# withcc3200.net
KiCad netlist of a schematic drawn in EAGLE
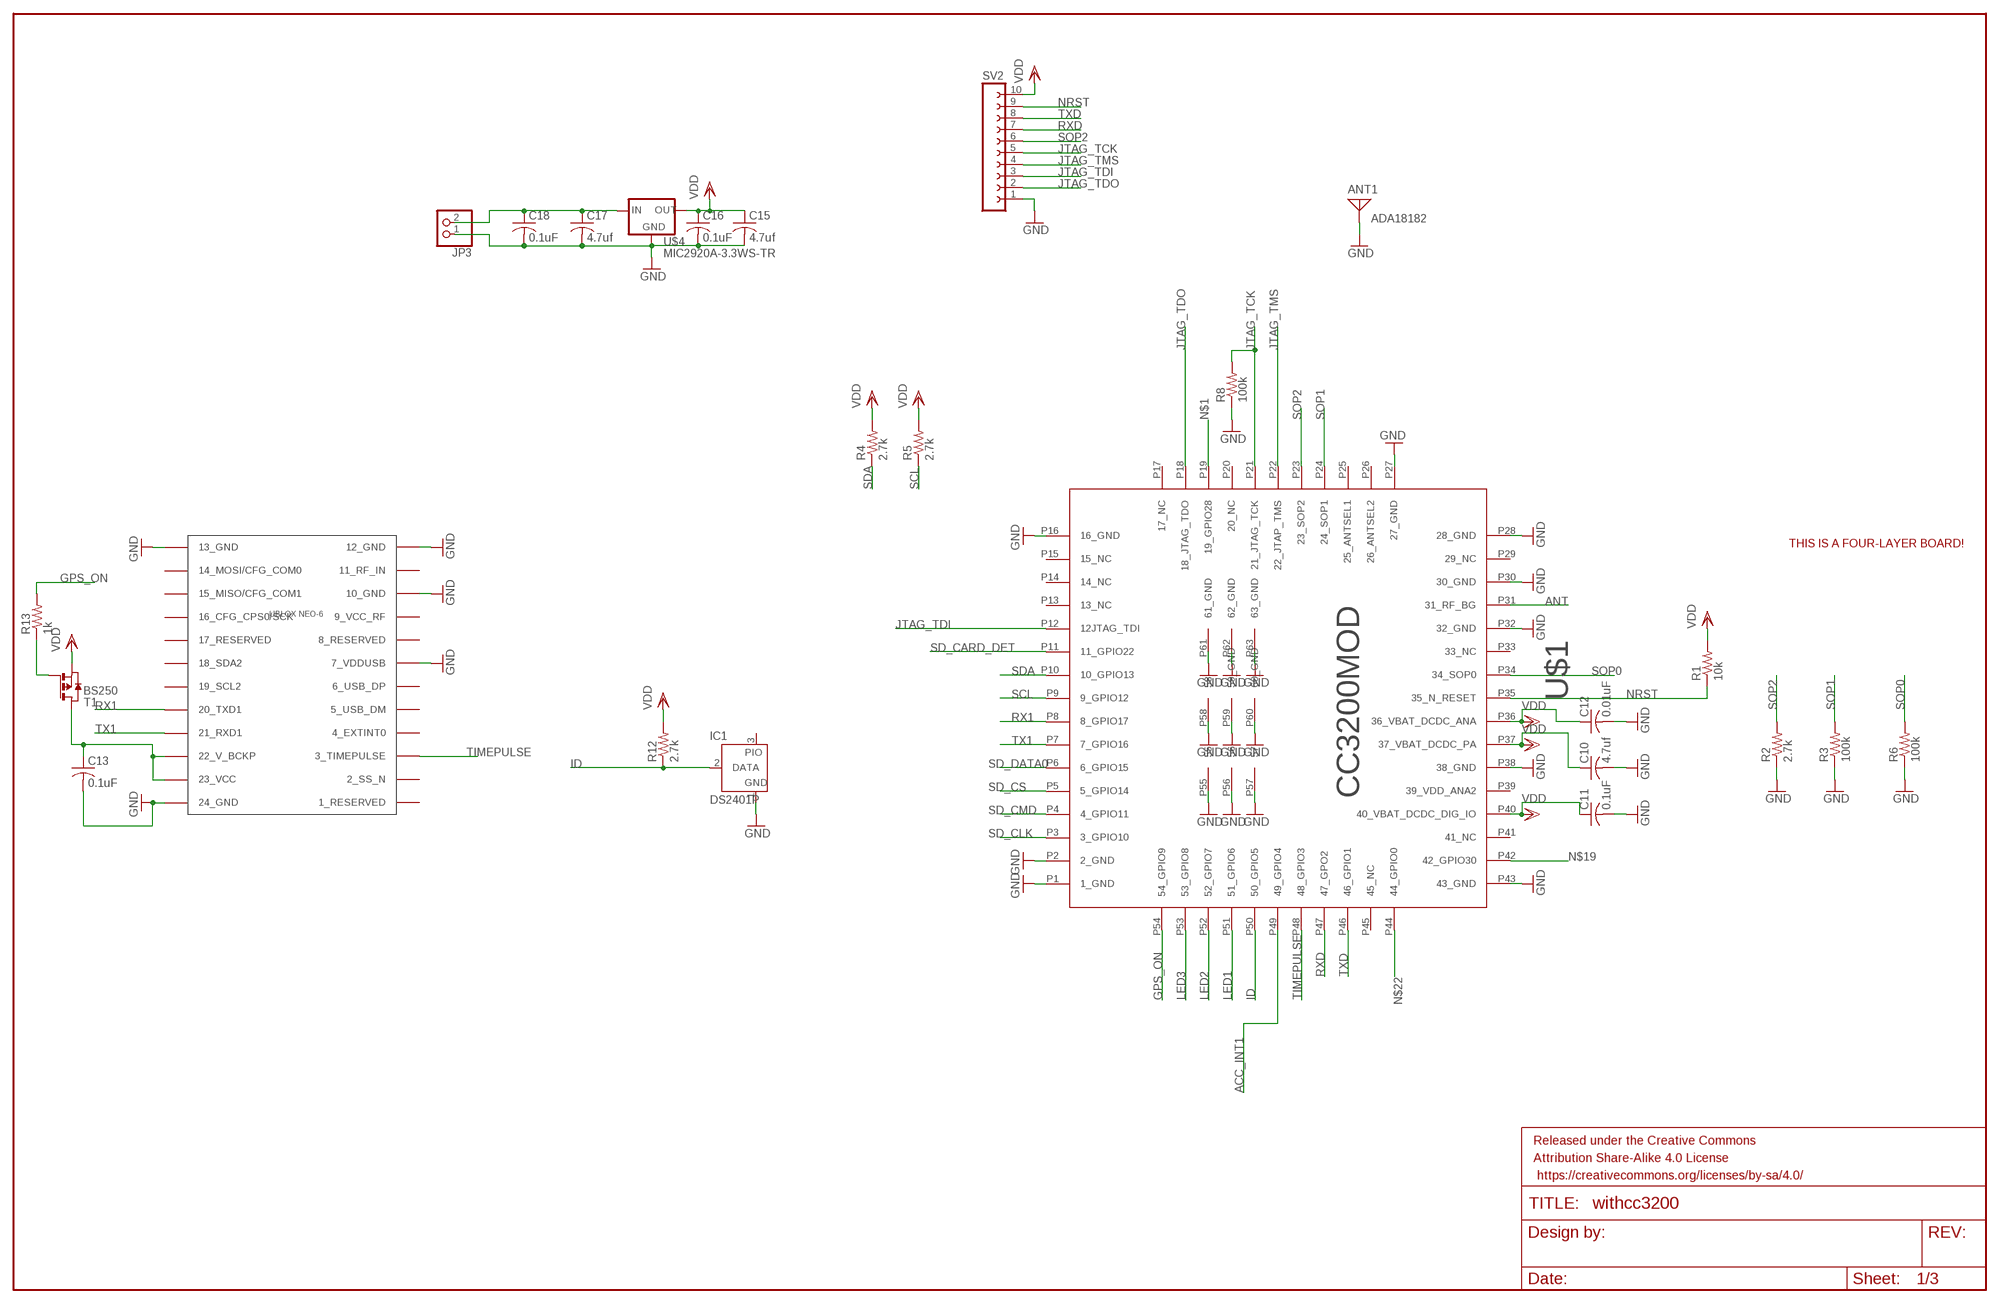
[diagram p0: schematic, sheet 1]
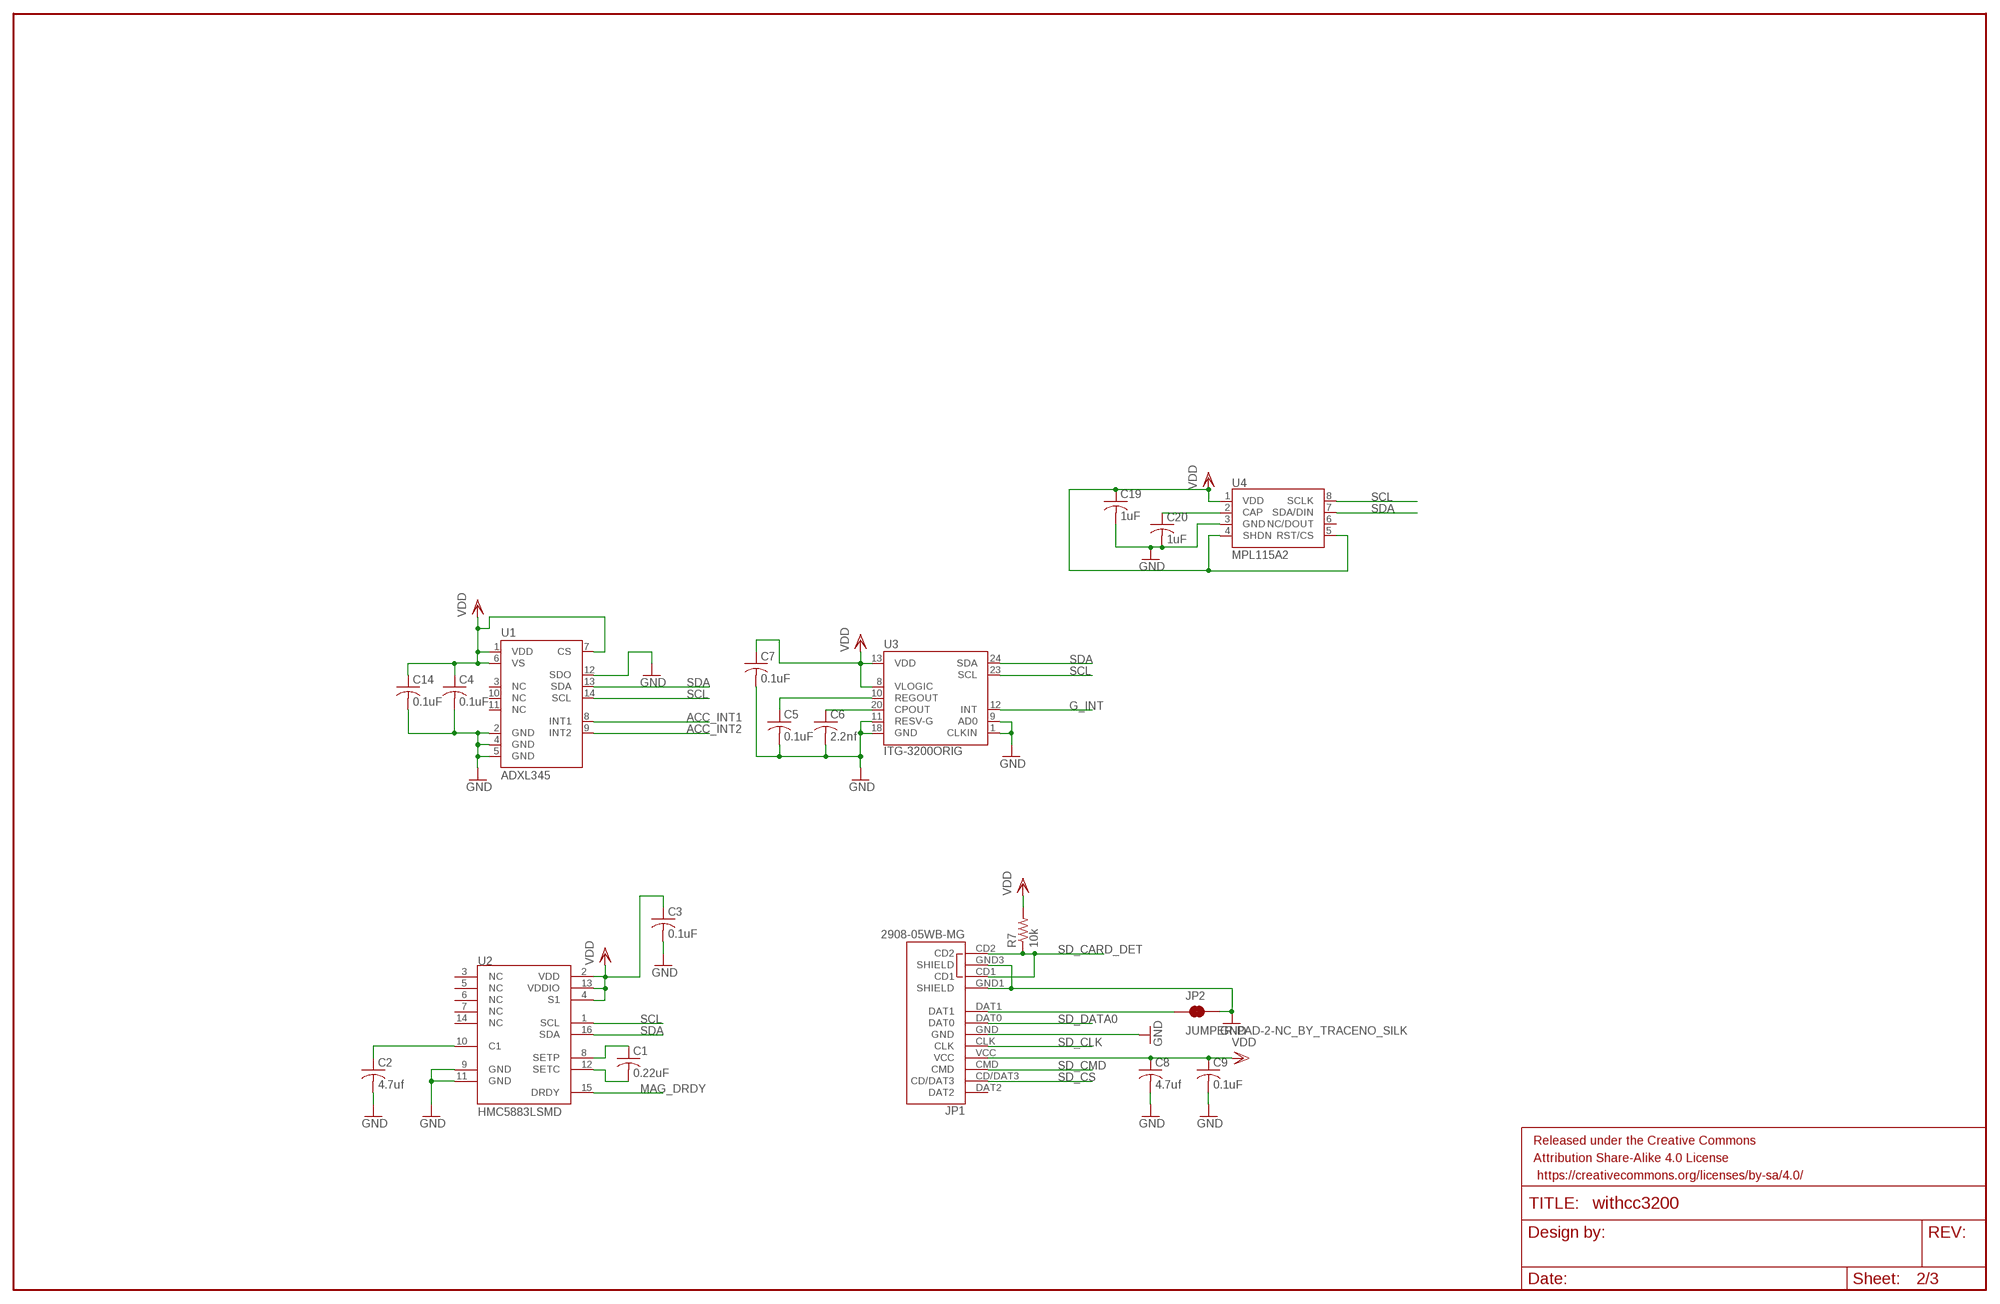
[diagram p1: schematic, sheet 2]
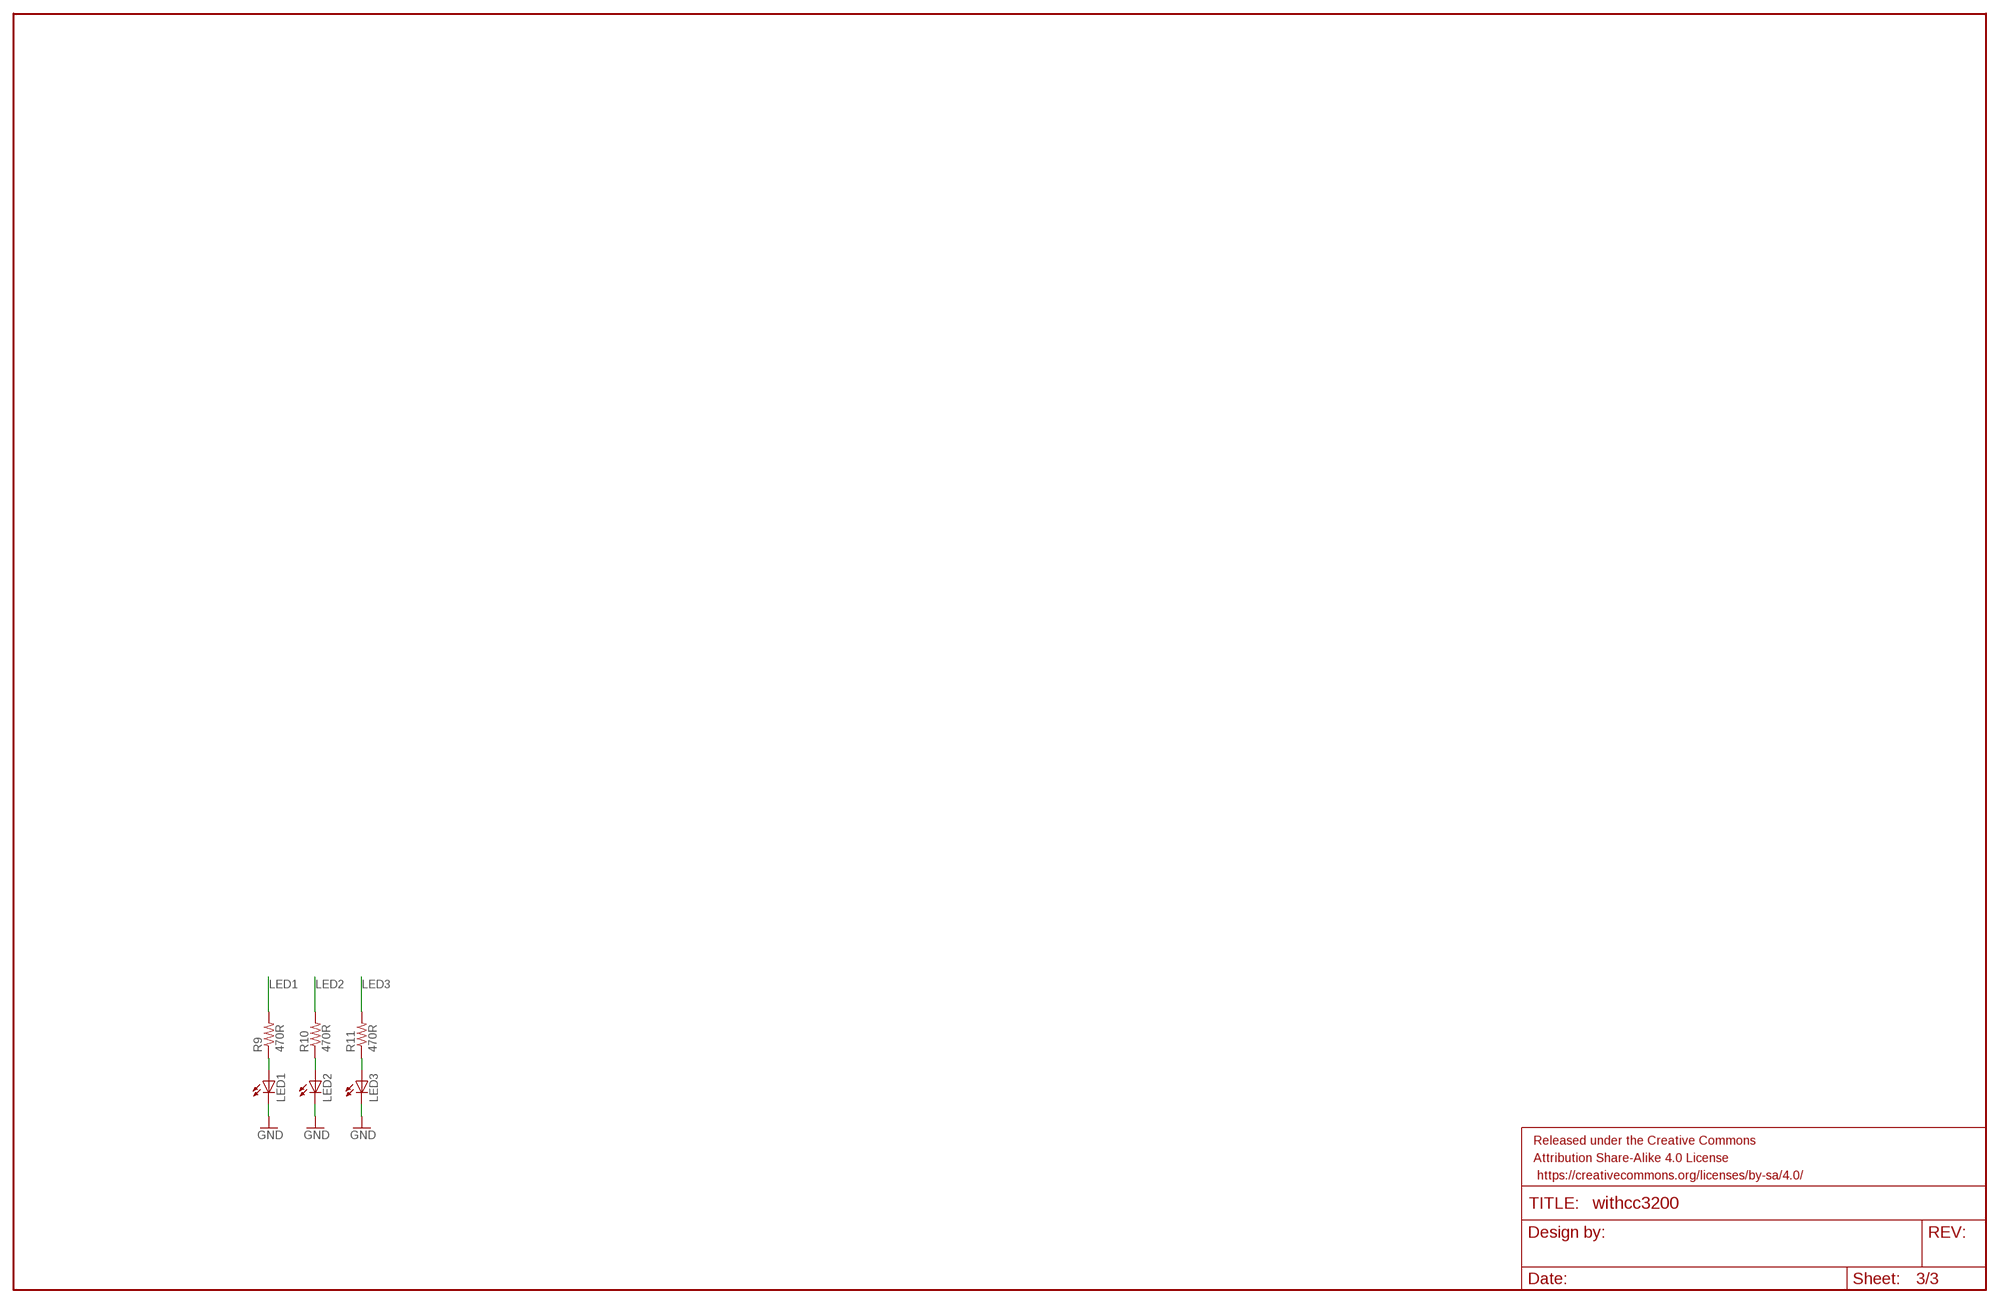
[diagram p2: schematic, sheet 3]

(export (version "E")
  (design (tool "Eeschema 10.0.6"))
  (components
    (comp (ref "C1")
      (value "0.22uF")
      (footprint "eagle-import:C0805K")
      (libsource (lib "eagle-import") (part "C-USC0805K"))
    )
    (comp (ref "C2")
      (value "4.7uf")
      (footprint "eagle-import:C0805K")
      (libsource (lib "eagle-import") (part "C-USC0805K"))
    )
    (comp (ref "C3")
      (value "0.1uF")
      (footprint "eagle-import:C0805K")
      (libsource (lib "eagle-import") (part "C-USC0805K"))
    )
    (comp (ref "C4")
      (value "0.1uF")
      (footprint "eagle-import:C0805K")
      (libsource (lib "eagle-import") (part "C-USC0805K"))
    )
    (comp (ref "C5")
      (value "0.1uF")
      (footprint "eagle-import:C0805K")
      (libsource (lib "eagle-import") (part "C-USC0805K"))
    )
    (comp (ref "C6")
      (value "2.2nf")
      (footprint "eagle-import:C0805K")
      (libsource (lib "eagle-import") (part "C-USC0805K"))
    )
    (comp (ref "C7")
      (value "0.1uF")
      (footprint "eagle-import:C0805K")
      (libsource (lib "eagle-import") (part "C-USC0805K"))
    )
    (comp (ref "C8")
      (value "4.7uf")
      (footprint "eagle-import:C0805K")
      (libsource (lib "eagle-import") (part "C-USC0805K"))
    )
    (comp (ref "C9")
      (value "0.1uF")
      (footprint "eagle-import:C0805K")
      (libsource (lib "eagle-import") (part "C-USC0805K"))
    )
    (comp (ref "C14")
      (value "0.1uF")
      (footprint "eagle-import:C0805K")
      (libsource (lib "eagle-import") (part "C-USC0805K"))
    )
    (comp (ref "C19")
      (value "1uF")
      (footprint "eagle-import:C0805K")
      (libsource (lib "eagle-import") (part "C-USC0805K"))
    )
    (comp (ref "C20")
      (value "1uF")
      (footprint "eagle-import:C0805K")
      (libsource (lib "eagle-import") (part "C-USC0805K"))
    )
    (comp (ref "FRAME2")
      (value "FRAME-LEDGER")
      (footprint "eagle-import:CREATIVE_COMMONS")
      (libsource (lib "eagle-import") (part "FRAME-LEDGER"))
    )
    (comp (ref "JP1")
      (value "2908-05WB-MG")
      (footprint "eagle-import:MICRO-SD-SOCKET-SDIO")
      (libsource (lib "eagle-import") (part "USD-SDIO-SOCKET"))
    )
    (comp (ref "JP2")
      (value "JUMPER-PAD-2-NC_BY_TRACENO_SILK")
      (footprint "eagle-import:PAD-JUMPER-2-NC_BY_TRACE_NO_SILK")
      (libsource (lib "eagle-import") (part "JUMPER-PAD-2-NC_BY_TRACENO_SILK"))
    )
    (comp (ref "R7")
      (value "10k")
      (footprint "eagle-import:R0603")
      (libsource (lib "eagle-import") (part "R-US_R0603"))
    )
    (comp (ref "U1")
      (value "ADXL345")
      (footprint "eagle-import:LGA14")
      (libsource (lib "eagle-import") (part "ADXL345"))
    )
    (comp (ref "U2")
      (value "HMC5883LSMD")
      (footprint "eagle-import:16LPCC")
      (libsource (lib "eagle-import") (part "HMC5883LSMD"))
    )
    (comp (ref "U3")
      (value "ITG-3200ORIG")
      (footprint "eagle-import:QFN-24")
      (libsource (lib "eagle-import") (part "ITG-3200ORIG"))
    )
    (comp (ref "U4")
      (value "MPL115A2")
      (footprint "eagle-import:LGA8")
      (libsource (lib "eagle-import") (part "MPL115A"))
    )
    (comp (ref "ANT1")
      (value "ADA18182")
      (footprint "eagle-import:PAD-01")
      (libsource (lib "eagle-import") (part "ANTENNA"))
    )
    (comp (ref "C10")
      (value "4.7uf")
      (footprint "eagle-import:C0805K")
      (libsource (lib "eagle-import") (part "C-USC0805K"))
    )
    (comp (ref "C11")
      (value "0.1uF")
      (footprint "eagle-import:C0805K")
      (libsource (lib "eagle-import") (part "C-USC0805K"))
    )
    (comp (ref "C12")
      (value "0.01uF")
      (footprint "eagle-import:C0805K")
      (libsource (lib "eagle-import") (part "C-USC0805K"))
    )
    (comp (ref "C13")
      (value "0.1uF")
      (footprint "eagle-import:C0805K")
      (libsource (lib "eagle-import") (part "C-USC0805K"))
    )
    (comp (ref "C15")
      (value "4.7uf")
      (footprint "eagle-import:C0805K")
      (libsource (lib "eagle-import") (part "C-USC0805K"))
    )
    (comp (ref "C16")
      (value "0.1uF")
      (footprint "eagle-import:C0805K")
      (libsource (lib "eagle-import") (part "C-USC0805K"))
    )
    (comp (ref "C17")
      (value "4.7uf")
      (footprint "eagle-import:C0805K")
      (libsource (lib "eagle-import") (part "C-USC0805K"))
    )
    (comp (ref "C18")
      (value "0.1uF")
      (footprint "eagle-import:C0805K")
      (libsource (lib "eagle-import") (part "C-USC0805K"))
    )
    (comp (ref "FRAME1")
      (value "FRAME-LEDGER")
      (footprint "eagle-import:CREATIVE_COMMONS")
      (libsource (lib "eagle-import") (part "FRAME-LEDGER"))
    )
    (comp (ref "IC1")
      (value "DS2401P")
      (footprint "eagle-import:TSOC6")
      (libsource (lib "eagle-import") (part "DS2405P"))
    )
    (comp (ref "JP3")
      (value "PINHD-1X2")
      (footprint "eagle-import:1X02")
      (libsource (lib "eagle-import") (part "PINHD-1X2"))
    )
    (comp (ref "R1")
      (value "10k")
      (footprint "eagle-import:R0603")
      (libsource (lib "eagle-import") (part "R-US_R0603"))
    )
    (comp (ref "R2")
      (value "2.7k")
      (footprint "eagle-import:R0603")
      (libsource (lib "eagle-import") (part "R-US_R0603"))
    )
    (comp (ref "R3")
      (value "100k")
      (footprint "eagle-import:R0603")
      (libsource (lib "eagle-import") (part "R-US_R0603"))
    )
    (comp (ref "R4")
      (value "2.7k")
      (footprint "eagle-import:R0603")
      (libsource (lib "eagle-import") (part "R-US_R0603"))
    )
    (comp (ref "R5")
      (value "2.7k")
      (footprint "eagle-import:R0603")
      (libsource (lib "eagle-import") (part "R-US_R0603"))
    )
    (comp (ref "R6")
      (value "100k")
      (footprint "eagle-import:R0603")
      (libsource (lib "eagle-import") (part "R-US_R0603"))
    )
    (comp (ref "R8")
      (value "100k")
      (footprint "eagle-import:R0603")
      (libsource (lib "eagle-import") (part "R-US_R0603"))
    )
    (comp (ref "R12")
      (value "2.7k")
      (footprint "eagle-import:R0603")
      (libsource (lib "eagle-import") (part "R-US_R0603"))
    )
    (comp (ref "R13")
      (value "1k")
      (footprint "eagle-import:R0603")
      (libsource (lib "eagle-import") (part "R-US_R0603"))
    )
    (comp (ref "SV2")
      (value "FE10-1")
      (footprint "eagle-import:FE10")
      (libsource (lib "eagle-import") (part "FE10-1"))
    )
    (comp (ref "T1")
      (value "BS250")
      (footprint "eagle-import:SOT-23")
      (libsource (lib "eagle-import") (part "PMOSSOT23"))
    )
    (comp (ref "U$1")
      (value "CC3200MOD")
      (footprint "eagle-import:CC3200MOD")
      (libsource (lib "eagle-import") (part "CC3200"))
    )
    (comp (ref "U$2")
      (value "UBLOX_NEO-7")
      (footprint "eagle-import:UBLOX_NEO-6P")
      (libsource (lib "eagle-import") (part "UBLOX_NEO-6"))
    )
    (comp (ref "U$3")
      (value "FOUR_LAYER_WARNING")
      (footprint "eagle-import:FOUR_LAYER_WARNING")
      (libsource (lib "eagle-import") (part "FOUR_LAYER_WARNING"))
    )
    (comp (ref "U$4")
      (value "MIC2920A-3.3WS-TR")
      (footprint "eagle-import:SOT223")
      (libsource (lib "eagle-import") (part "V_REG_MIC2920"))
    )
    (comp (ref "FRAME3")
      (value "FRAME-LEDGER")
      (footprint "eagle-import:CREATIVE_COMMONS")
      (libsource (lib "eagle-import") (part "FRAME-LEDGER"))
    )
    (comp (ref "LED1")
      (value "LEDCHIPLED_0805")
      (footprint "eagle-import:CHIPLED_0805")
      (libsource (lib "eagle-import") (part "LEDCHIPLED_0805"))
    )
    (comp (ref "LED2")
      (value "LEDCHIPLED_0805")
      (footprint "eagle-import:CHIPLED_0805")
      (libsource (lib "eagle-import") (part "LEDCHIPLED_0805"))
    )
    (comp (ref "LED3")
      (value "LEDCHIPLED_0805")
      (footprint "eagle-import:CHIPLED_0805")
      (libsource (lib "eagle-import") (part "LEDCHIPLED_0805"))
    )
    (comp (ref "R9")
      (value "470R")
      (footprint "eagle-import:R0603")
      (libsource (lib "eagle-import") (part "R-US_R0603"))
    )
    (comp (ref "R10")
      (value "470R")
      (footprint "eagle-import:R0603")
      (libsource (lib "eagle-import") (part "R-US_R0603"))
    )
    (comp (ref "R11")
      (value "470R")
      (footprint "eagle-import:R0603")
      (libsource (lib "eagle-import") (part "R-US_R0603"))
    )
  )
  (nets
    (net (code "1") (name "ACC_INT1") (class "Default")
      (node (ref "U$1") (pin "P49") (pinfunction "49_GPIO4_P49") (pintype "bidirectional"))
      (node (ref "U1") (pin "8") (pinfunction "INT1_8") (pintype "bidirectional"))
    )
    (net (code "2") (name "ACC_INT2") (class "Default")
      (node (ref "U1") (pin "9") (pinfunction "INT2_9") (pintype "bidirectional"))
    )
    (net (code "3") (name "ANT") (class "Default")
      (node (ref "U$1") (pin "P31") (pinfunction "31_RF_BG_P31") (pintype "bidirectional"))
    )
    (net (code "4") (name "GND") (class "Default")
      (node (ref "ANT1") (pin "1") (pinfunction "1_1") (pintype "output"))
      (node (ref "C10") (pin "2") (pinfunction "2_2") (pintype "passive"))
      (node (ref "C11") (pin "2") (pinfunction "2_2") (pintype "passive"))
      (node (ref "C12") (pin "2") (pinfunction "2_2") (pintype "passive"))
      (node (ref "C13") (pin "2") (pinfunction "2_2") (pintype "passive"))
      (node (ref "C14") (pin "2") (pinfunction "2_2") (pintype "passive"))
      (node (ref "C15") (pin "2") (pinfunction "2_2") (pintype "passive"))
      (node (ref "C16") (pin "2") (pinfunction "2_2") (pintype "passive"))
      (node (ref "C17") (pin "2") (pinfunction "2_2") (pintype "passive"))
      (node (ref "C18") (pin "2") (pinfunction "2_2") (pintype "passive"))
      (node (ref "C19") (pin "2") (pinfunction "2_2") (pintype "passive"))
      (node (ref "C2") (pin "2") (pinfunction "2_2") (pintype "passive"))
      (node (ref "C20") (pin "2") (pinfunction "2_2") (pintype "passive"))
      (node (ref "C3") (pin "2") (pinfunction "2_2") (pintype "passive"))
      (node (ref "C4") (pin "2") (pinfunction "2_2") (pintype "passive"))
      (node (ref "C5") (pin "2") (pinfunction "2_2") (pintype "passive"))
      (node (ref "C6") (pin "2") (pinfunction "2_2") (pintype "passive"))
      (node (ref "C7") (pin "2") (pinfunction "2_2") (pintype "passive"))
      (node (ref "C8") (pin "2") (pinfunction "2_2") (pintype "passive"))
      (node (ref "C9") (pin "2") (pinfunction "2_2") (pintype "passive"))
      (node (ref "IC1") (pin "1") (pinfunction "GND_1") (pintype "passive"))
      (node (ref "JP1") (pin "GND") (pinfunction "GND_GND") (pintype "bidirectional"))
      (node (ref "JP1") (pin "GND1") (pinfunction "SHIELD_GND1") (pintype "bidirectional"))
      (node (ref "JP1") (pin "GND3") (pinfunction "SHIELD_GND3") (pintype "bidirectional"))
      (node (ref "JP2") (pin "2") (pinfunction "2_2") (pintype "passive"))
      (node (ref "JP3") (pin "1") (pinfunction "1_1") (pintype "passive"))
      (node (ref "LED1") (pin "C") (pinfunction "C_C") (pintype "passive"))
      (node (ref "LED2") (pin "C") (pinfunction "C_C") (pintype "passive"))
      (node (ref "LED3") (pin "C") (pinfunction "C_C") (pintype "passive"))
      (node (ref "R2") (pin "1") (pinfunction "1_1") (pintype "passive"))
      (node (ref "R3") (pin "1") (pinfunction "1_1") (pintype "passive"))
      (node (ref "R6") (pin "1") (pinfunction "1_1") (pintype "passive"))
      (node (ref "R8") (pin "1") (pinfunction "1_1") (pintype "passive"))
      (node (ref "SV2") (pin "1") (pinfunction "1_1") (pintype "passive"))
      (node (ref "U$1") (pin "P1") (pinfunction "1_GND_P1") (pintype "bidirectional"))
      (node (ref "U$1") (pin "P16") (pinfunction "16_GND_P16") (pintype "bidirectional"))
      (node (ref "U$1") (pin "P2") (pinfunction "2_GND_P2") (pintype "bidirectional"))
      (node (ref "U$1") (pin "P27") (pinfunction "27_GND_P27") (pintype "bidirectional"))
      (node (ref "U$1") (pin "P28") (pinfunction "28_GND_P28") (pintype "bidirectional"))
      (node (ref "U$1") (pin "P30") (pinfunction "30_GND_P30") (pintype "bidirectional"))
      (node (ref "U$1") (pin "P32") (pinfunction "32_GND_P32") (pintype "bidirectional"))
      (node (ref "U$1") (pin "P38") (pinfunction "38_GND_P38") (pintype "bidirectional"))
      (node (ref "U$1") (pin "P43") (pinfunction "43_GND_P43") (pintype "bidirectional"))
      (node (ref "U$1") (pin "P55") (pinfunction "55_P55") (pintype "bidirectional"))
      (node (ref "U$1") (pin "P56") (pinfunction "56_P56") (pintype "bidirectional"))
      (node (ref "U$1") (pin "P57") (pinfunction "57_P57") (pintype "bidirectional"))
      (node (ref "U$1") (pin "P58") (pinfunction "58_P58") (pintype "bidirectional"))
      (node (ref "U$1") (pin "P59") (pinfunction "59_GND_P59") (pintype "bidirectional"))
      (node (ref "U$1") (pin "P60") (pinfunction "60_GND_P60") (pintype "bidirectional"))
      (node (ref "U$1") (pin "P61") (pinfunction "61_GND_P61") (pintype "bidirectional"))
      (node (ref "U$1") (pin "P62") (pinfunction "62_GND_P62") (pintype "bidirectional"))
      (node (ref "U$1") (pin "P63") (pinfunction "63_GND_P63") (pintype "bidirectional"))
      (node (ref "U$2") (pin "10_GND") (pinfunction "10_GND_10_GND") (pintype "bidirectional"))
      (node (ref "U$2") (pin "12_GND") (pinfunction "12_GND_12_GND") (pintype "bidirectional"))
      (node (ref "U$2") (pin "13_GND") (pinfunction "13_GND_13_GND") (pintype "bidirectional"))
      (node (ref "U$2") (pin "24_GND") (pinfunction "24_GND_24_GND") (pintype "bidirectional"))
      (node (ref "U$2") (pin "7_VDDUSB") (pinfunction "7_VDDUSB_7_VDDUSB") (pintype "bidirectional"))
      (node (ref "U$4") (pin "2") (pinfunction "GND_2") (pintype "input"))
      (node (ref "U1") (pin "12") (pinfunction "SDO_12") (pintype "bidirectional"))
      (node (ref "U1") (pin "2") (pinfunction "GND_2") (pintype "bidirectional"))
      (node (ref "U1") (pin "4") (pinfunction "GND_4") (pintype "bidirectional"))
      (node (ref "U1") (pin "5") (pinfunction "GND_5") (pintype "bidirectional"))
      (node (ref "U2") (pin "11") (pinfunction "GND_11") (pintype "bidirectional"))
      (node (ref "U2") (pin "9") (pinfunction "GND_9") (pintype "bidirectional"))
      (node (ref "U3") (pin "1") (pinfunction "CLKIN_1") (pintype "bidirectional"))
      (node (ref "U3") (pin "11") (pinfunction "RESV-G_11") (pintype "bidirectional"))
      (node (ref "U3") (pin "18") (pinfunction "GND_18") (pintype "bidirectional"))
      (node (ref "U3") (pin "9") (pinfunction "AD0_9") (pintype "bidirectional"))
      (node (ref "U4") (pin "3") (pinfunction "GND_3") (pintype "bidirectional"))
    )
    (net (code "5") (name "GPS_ON") (class "Default")
      (node (ref "R13") (pin "2") (pinfunction "2_2") (pintype "passive"))
      (node (ref "U$1") (pin "P54") (pinfunction "54_GPIO9_P54") (pintype "bidirectional"))
    )
    (net (code "6") (name "G_INT") (class "Default")
      (node (ref "U3") (pin "12") (pinfunction "INT_12") (pintype "bidirectional"))
    )
    (net (code "7") (name "ID") (class "Default")
      (node (ref "IC1") (pin "2") (pinfunction "DATA_2") (pintype "input"))
      (node (ref "R12") (pin "1") (pinfunction "1_1") (pintype "passive"))
      (node (ref "U$1") (pin "P50") (pinfunction "50_GPIO5_P50") (pintype "bidirectional"))
    )
    (net (code "8") (name "JTAG_TCK") (class "Default")
      (node (ref "R8") (pin "2") (pinfunction "2_2") (pintype "passive"))
      (node (ref "SV2") (pin "5") (pinfunction "5_5") (pintype "passive"))
      (node (ref "U$1") (pin "P21") (pinfunction "21_JTAG_TCK_P21") (pintype "bidirectional"))
    )
    (net (code "9") (name "JTAG_TDI") (class "Default")
      (node (ref "SV2") (pin "3") (pinfunction "3_3") (pintype "passive"))
      (node (ref "U$1") (pin "P12") (pinfunction "12JTAG_TDI_P12") (pintype "bidirectional"))
    )
    (net (code "10") (name "JTAG_TDO") (class "Default")
      (node (ref "SV2") (pin "2") (pinfunction "2_2") (pintype "passive"))
      (node (ref "U$1") (pin "P18") (pinfunction "18_JTAG_TDO_P18") (pintype "bidirectional"))
    )
    (net (code "11") (name "JTAG_TMS") (class "Default")
      (node (ref "SV2") (pin "4") (pinfunction "4_4") (pintype "passive"))
      (node (ref "U$1") (pin "P22") (pinfunction "22_JTAP_TMS_P22") (pintype "bidirectional"))
    )
    (net (code "12") (name "LED1") (class "Default")
      (node (ref "R9") (pin "2") (pinfunction "2_2") (pintype "passive"))
      (node (ref "U$1") (pin "P51") (pinfunction "51_GPIO6_P51") (pintype "bidirectional"))
    )
    (net (code "13") (name "LED2") (class "Default")
      (node (ref "R10") (pin "2") (pinfunction "2_2") (pintype "passive"))
      (node (ref "U$1") (pin "P52") (pinfunction "52_GPIO7_P52") (pintype "bidirectional"))
    )
    (net (code "14") (name "LED3") (class "Default")
      (node (ref "R11") (pin "2") (pinfunction "2_2") (pintype "passive"))
      (node (ref "U$1") (pin "P53") (pinfunction "53_GPIO8_P53") (pintype "bidirectional"))
    )
    (net (code "15") (name "MAG_DRDY") (class "Default")
      (node (ref "U2") (pin "15") (pinfunction "DRDY_15") (pintype "bidirectional"))
    )
    (net (code "16") (name "N$1") (class "Default")
      (node (ref "U$1") (pin "P19") (pinfunction "19_GPIO28_P19") (pintype "bidirectional"))
    )
    (net (code "17") (name "N$19") (class "Default")
      (node (ref "U$1") (pin "P42") (pinfunction "42_GPIO30_P42") (pintype "bidirectional"))
    )
    (net (code "18") (name "N$22") (class "Default")
      (node (ref "U$1") (pin "P44") (pinfunction "44_GPIO0_P44") (pintype "bidirectional"))
    )
    (net (code "19") (name "NRST") (class "Default")
      (node (ref "R1") (pin "1") (pinfunction "1_1") (pintype "passive"))
      (node (ref "SV2") (pin "9") (pinfunction "9_9") (pintype "passive"))
      (node (ref "U$1") (pin "P35") (pinfunction "35_N_RESET_P35") (pintype "bidirectional"))
    )
    (net (code "20") (name "Net-(JP1-PadDAT1)") (class "Default")
      (node (ref "JP1") (pin "DAT1") (pinfunction "DAT1_DAT1") (pintype "bidirectional"))
      (node (ref "JP2") (pin "1") (pinfunction "1_1") (pintype "passive"))
    )
    (net (code "21") (name "Net-(LED1-PadA)") (class "Default")
      (node (ref "LED1") (pin "A") (pinfunction "A_A") (pintype "passive"))
      (node (ref "R9") (pin "1") (pinfunction "1_1") (pintype "passive"))
    )
    (net (code "22") (name "Net-(LED2-PadA)") (class "Default")
      (node (ref "LED2") (pin "A") (pinfunction "A_A") (pintype "passive"))
      (node (ref "R10") (pin "1") (pinfunction "1_1") (pintype "passive"))
    )
    (net (code "23") (name "Net-(LED3-PadA)") (class "Default")
      (node (ref "LED3") (pin "A") (pinfunction "A_A") (pintype "passive"))
      (node (ref "R11") (pin "1") (pinfunction "1_1") (pintype "passive"))
    )
    (net (code "24") (name "Net-(T1-D)") (class "Default")
      (node (ref "C13") (pin "1") (pinfunction "1_1") (pintype "passive"))
      (node (ref "T1") (pin "1") (pinfunction "D_1") (pintype "passive"))
      (node (ref "U$2") (pin "22_V_BCKP") (pinfunction "22_V_BCKP_22_V_BCKP") (pintype "bidirectional"))
      (node (ref "U$2") (pin "23_VCC") (pinfunction "23_VCC_23_VCC") (pintype "bidirectional"))
    )
    (net (code "25") (name "Net-(T1-G)") (class "Default")
      (node (ref "R13") (pin "1") (pinfunction "1_1") (pintype "passive"))
      (node (ref "T1") (pin "3") (pinfunction "G_3") (pintype "passive"))
    )
    (net (code "26") (name "Net-(U$4-IN)") (class "Default")
      (node (ref "C17") (pin "1") (pinfunction "1_1") (pintype "passive"))
      (node (ref "C18") (pin "1") (pinfunction "1_1") (pintype "passive"))
      (node (ref "JP3") (pin "2") (pinfunction "2_2") (pintype "passive"))
      (node (ref "U$4") (pin "1") (pinfunction "IN_1") (pintype "input"))
    )
    (net (code "27") (name "Net-(U2-C1)") (class "Default")
      (node (ref "C2") (pin "1") (pinfunction "1_1") (pintype "passive"))
      (node (ref "U2") (pin "10") (pinfunction "C1_10") (pintype "bidirectional"))
    )
    (net (code "28") (name "Net-(U2-SETC)") (class "Default")
      (node (ref "C1") (pin "2") (pinfunction "2_2") (pintype "passive"))
      (node (ref "U2") (pin "12") (pinfunction "SETC_12") (pintype "bidirectional"))
    )
    (net (code "29") (name "Net-(U2-SETP)") (class "Default")
      (node (ref "C1") (pin "1") (pinfunction "1_1") (pintype "passive"))
      (node (ref "U2") (pin "8") (pinfunction "SETP_8") (pintype "bidirectional"))
    )
    (net (code "30") (name "Net-(U3-CPOUT)") (class "Default")
      (node (ref "C6") (pin "1") (pinfunction "1_1") (pintype "passive"))
      (node (ref "U3") (pin "20") (pinfunction "CPOUT_20") (pintype "bidirectional"))
    )
    (net (code "31") (name "Net-(U3-REGOUT)") (class "Default")
      (node (ref "C5") (pin "1") (pinfunction "1_1") (pintype "passive"))
      (node (ref "U3") (pin "10") (pinfunction "REGOUT_10") (pintype "bidirectional"))
    )
    (net (code "32") (name "Net-(U4-CAP)") (class "Default")
      (node (ref "C20") (pin "1") (pinfunction "1_1") (pintype "passive"))
      (node (ref "U4") (pin "2") (pinfunction "CAP_2") (pintype "bidirectional"))
    )
    (net (code "33") (name "RX1") (class "Default")
      (node (ref "U$1") (pin "P8") (pinfunction "8_GPIO17_P8") (pintype "bidirectional"))
      (node (ref "U$2") (pin "20_TXD1") (pinfunction "20_TXD1_20_TXD1") (pintype "bidirectional"))
    )
    (net (code "34") (name "RXD") (class "Default")
      (node (ref "SV2") (pin "7") (pinfunction "7_7") (pintype "passive"))
      (node (ref "U$1") (pin "P47") (pinfunction "47_GPO2_P47") (pintype "bidirectional"))
    )
    (net (code "35") (name "SCL") (class "Default")
      (node (ref "R5") (pin "1") (pinfunction "1_1") (pintype "passive"))
      (node (ref "U$1") (pin "P9") (pinfunction "9_GPIO12_P9") (pintype "bidirectional"))
      (node (ref "U1") (pin "14") (pinfunction "SCL_14") (pintype "bidirectional"))
      (node (ref "U2") (pin "1") (pinfunction "SCL_1") (pintype "bidirectional"))
      (node (ref "U3") (pin "23") (pinfunction "SCL_23") (pintype "bidirectional"))
      (node (ref "U4") (pin "8") (pinfunction "SCLK_8") (pintype "bidirectional"))
    )
    (net (code "36") (name "SDA") (class "Default")
      (node (ref "R4") (pin "1") (pinfunction "1_1") (pintype "passive"))
      (node (ref "U$1") (pin "P10") (pinfunction "10_GPIO13_P10") (pintype "bidirectional"))
      (node (ref "U1") (pin "13") (pinfunction "SDA_13") (pintype "bidirectional"))
      (node (ref "U2") (pin "16") (pinfunction "SDA_16") (pintype "bidirectional"))
      (node (ref "U3") (pin "24") (pinfunction "SDA_24") (pintype "bidirectional"))
      (node (ref "U4") (pin "7") (pinfunction "SDA/DIN_7") (pintype "bidirectional"))
    )
    (net (code "37") (name "SD_CARD_DET") (class "Default")
      (node (ref "JP1") (pin "CD1") (pinfunction "CD1_CD1") (pintype "bidirectional"))
      (node (ref "JP1") (pin "CD2") (pinfunction "CD2_CD2") (pintype "bidirectional"))
      (node (ref "R7") (pin "1") (pinfunction "1_1") (pintype "passive"))
      (node (ref "U$1") (pin "P11") (pinfunction "11_GPIO22_P11") (pintype "bidirectional"))
    )
    (net (code "38") (name "SD_CLK") (class "Default")
      (node (ref "JP1") (pin "CLK") (pinfunction "CLK_CLK") (pintype "bidirectional"))
      (node (ref "U$1") (pin "P3") (pinfunction "3_GPIO10_P3") (pintype "bidirectional"))
    )
    (net (code "39") (name "SD_CMD") (class "Default")
      (node (ref "JP1") (pin "CMD") (pinfunction "CMD_CMD") (pintype "bidirectional"))
      (node (ref "U$1") (pin "P4") (pinfunction "4_GPIO11_P4") (pintype "bidirectional"))
    )
    (net (code "40") (name "SD_CS") (class "Default")
      (node (ref "JP1") (pin "CD/DAT3") (pinfunction "CD/DAT3_CD/DAT3") (pintype "bidirectional"))
      (node (ref "U$1") (pin "P5") (pinfunction "5_GPIO14_P5") (pintype "bidirectional"))
    )
    (net (code "41") (name "SD_DATA0") (class "Default")
      (node (ref "JP1") (pin "DAT0") (pinfunction "DAT0_DAT0") (pintype "bidirectional"))
      (node (ref "U$1") (pin "P6") (pinfunction "6_GPIO15_P6") (pintype "bidirectional"))
    )
    (net (code "42") (name "SOP0") (class "Default")
      (node (ref "R6") (pin "2") (pinfunction "2_2") (pintype "passive"))
      (node (ref "U$1") (pin "P34") (pinfunction "34_SOP0_P34") (pintype "bidirectional"))
    )
    (net (code "43") (name "SOP1") (class "Default")
      (node (ref "R3") (pin "2") (pinfunction "2_2") (pintype "passive"))
      (node (ref "U$1") (pin "P24") (pinfunction "24_SOP1_P24") (pintype "bidirectional"))
    )
    (net (code "44") (name "SOP2") (class "Default")
      (node (ref "R2") (pin "2") (pinfunction "2_2") (pintype "passive"))
      (node (ref "SV2") (pin "6") (pinfunction "6_6") (pintype "passive"))
      (node (ref "U$1") (pin "P23") (pinfunction "23_SOP2_P23") (pintype "bidirectional"))
    )
    (net (code "45") (name "TIMEPULSE") (class "Default")
      (node (ref "U$1") (pin "P48") (pinfunction "48_GPIO3_P48") (pintype "bidirectional"))
      (node (ref "U$2") (pin "3_TIMEPULSE") (pinfunction "3_TIMEPULSE_3_TIMEPULSE") (pintype "bidirectional"))
    )
    (net (code "46") (name "TX1") (class "Default")
      (node (ref "U$1") (pin "P7") (pinfunction "7_GPIO16_P7") (pintype "bidirectional"))
      (node (ref "U$2") (pin "21_RXD1") (pinfunction "21_RXD1_21_RXD1") (pintype "bidirectional"))
    )
    (net (code "47") (name "TXD") (class "Default")
      (node (ref "SV2") (pin "8") (pinfunction "8_8") (pintype "passive"))
      (node (ref "U$1") (pin "P46") (pinfunction "46_GPIO1_P46") (pintype "bidirectional"))
    )
    (net (code "48") (name "VDD") (class "Default")
      (node (ref "C10") (pin "1") (pinfunction "1_1") (pintype "passive"))
      (node (ref "C11") (pin "1") (pinfunction "1_1") (pintype "passive"))
      (node (ref "C12") (pin "1") (pinfunction "1_1") (pintype "passive"))
      (node (ref "C14") (pin "1") (pinfunction "1_1") (pintype "passive"))
      (node (ref "C15") (pin "1") (pinfunction "1_1") (pintype "passive"))
      (node (ref "C16") (pin "1") (pinfunction "1_1") (pintype "passive"))
      (node (ref "C19") (pin "1") (pinfunction "1_1") (pintype "passive"))
      (node (ref "C3") (pin "1") (pinfunction "1_1") (pintype "passive"))
      (node (ref "C4") (pin "1") (pinfunction "1_1") (pintype "passive"))
      (node (ref "C7") (pin "1") (pinfunction "1_1") (pintype "passive"))
      (node (ref "C8") (pin "1") (pinfunction "1_1") (pintype "passive"))
      (node (ref "C9") (pin "1") (pinfunction "1_1") (pintype "passive"))
      (node (ref "JP1") (pin "VCC") (pinfunction "VCC_VCC") (pintype "bidirectional"))
      (node (ref "R1") (pin "2") (pinfunction "2_2") (pintype "passive"))
      (node (ref "R12") (pin "2") (pinfunction "2_2") (pintype "passive"))
      (node (ref "R4") (pin "2") (pinfunction "2_2") (pintype "passive"))
      (node (ref "R5") (pin "2") (pinfunction "2_2") (pintype "passive"))
      (node (ref "R7") (pin "2") (pinfunction "2_2") (pintype "passive"))
      (node (ref "SV2") (pin "10") (pinfunction "10_10") (pintype "passive"))
      (node (ref "T1") (pin "2") (pinfunction "S_2") (pintype "passive"))
      (node (ref "U$1") (pin "P36") (pinfunction "36_VBAT_DCDC_ANA_P36") (pintype "bidirectional"))
      (node (ref "U$1") (pin "P37") (pinfunction "37_VBAT_DCDC_PA_P37") (pintype "bidirectional"))
      (node (ref "U$1") (pin "P40") (pinfunction "40_VBAT_DCDC_DIG_IO_P40") (pintype "bidirectional"))
      (node (ref "U$4") (pin "3") (pinfunction "OUT_3") (pintype "passive"))
      (node (ref "U1") (pin "1") (pinfunction "VDD_1") (pintype "bidirectional"))
      (node (ref "U1") (pin "6") (pinfunction "VS_6") (pintype "bidirectional"))
      (node (ref "U1") (pin "7") (pinfunction "CS_7") (pintype "bidirectional"))
      (node (ref "U2") (pin "13") (pinfunction "VDDIO_13") (pintype "bidirectional"))
      (node (ref "U2") (pin "2") (pinfunction "VDD_2") (pintype "bidirectional"))
      (node (ref "U2") (pin "4") (pinfunction "S1_4") (pintype "bidirectional"))
      (node (ref "U3") (pin "13") (pinfunction "VDD_13") (pintype "bidirectional"))
      (node (ref "U3") (pin "8") (pinfunction "VLOGIC_8") (pintype "bidirectional"))
      (node (ref "U4") (pin "1") (pinfunction "VDD_1") (pintype "bidirectional"))
      (node (ref "U4") (pin "4") (pinfunction "SHDN_4") (pintype "bidirectional"))
      (node (ref "U4") (pin "5") (pinfunction "RST/CS_5") (pintype "bidirectional"))
    )
    (net (code "49") (name "unconnected-(IC1-PIO-Pad3)") (class "Default")
      (node (ref "IC1") (pin "3") (pinfunction "PIO_3") (pintype "passive"))
    )
    (net (code "50") (name "unconnected-(JP1-PadDAT2)") (class "Default")
      (node (ref "JP1") (pin "DAT2") (pinfunction "DAT2_DAT2") (pintype "bidirectional"))
    )
    (net (code "51") (name "unconnected-(U$1-13_NC-PadP13)") (class "Default")
      (node (ref "U$1") (pin "P13") (pinfunction "13_NC_P13") (pintype "bidirectional"))
    )
    (net (code "52") (name "unconnected-(U$1-14_NC-PadP14)") (class "Default")
      (node (ref "U$1") (pin "P14") (pinfunction "14_NC_P14") (pintype "bidirectional"))
    )
    (net (code "53") (name "unconnected-(U$1-15_NC-PadP15)") (class "Default")
      (node (ref "U$1") (pin "P15") (pinfunction "15_NC_P15") (pintype "bidirectional"))
    )
    (net (code "54") (name "unconnected-(U$1-17_NC-PadP17)") (class "Default")
      (node (ref "U$1") (pin "P17") (pinfunction "17_NC_P17") (pintype "bidirectional"))
    )
    (net (code "55") (name "unconnected-(U$1-20_NC-PadP20)") (class "Default")
      (node (ref "U$1") (pin "P20") (pinfunction "20_NC_P20") (pintype "bidirectional"))
    )
    (net (code "56") (name "unconnected-(U$1-25_ANTSEL1-PadP25)") (class "Default")
      (node (ref "U$1") (pin "P25") (pinfunction "25_ANTSEL1_P25") (pintype "bidirectional"))
    )
    (net (code "57") (name "unconnected-(U$1-26_ANTSEL2-PadP26)") (class "Default")
      (node (ref "U$1") (pin "P26") (pinfunction "26_ANTSEL2_P26") (pintype "bidirectional"))
    )
    (net (code "58") (name "unconnected-(U$1-29_NC-PadP29)") (class "Default")
      (node (ref "U$1") (pin "P29") (pinfunction "29_NC_P29") (pintype "bidirectional"))
    )
    (net (code "59") (name "unconnected-(U$1-33_NC-PadP33)") (class "Default")
      (node (ref "U$1") (pin "P33") (pinfunction "33_NC_P33") (pintype "bidirectional"))
    )
    (net (code "60") (name "unconnected-(U$1-39_VDD_ANA2-PadP39)") (class "Default")
      (node (ref "U$1") (pin "P39") (pinfunction "39_VDD_ANA2_P39") (pintype "bidirectional"))
    )
    (net (code "61") (name "unconnected-(U$1-41_NC-PadP41)") (class "Default")
      (node (ref "U$1") (pin "P41") (pinfunction "41_NC_P41") (pintype "bidirectional"))
    )
    (net (code "62") (name "unconnected-(U$1-45_NC-PadP45)") (class "Default")
      (node (ref "U$1") (pin "P45") (pinfunction "45_NC_P45") (pintype "bidirectional"))
    )
    (net (code "63") (name "unconnected-(U$2-Pad1_RESERVED)") (class "Default")
      (node (ref "U$2") (pin "1_RESERVED") (pinfunction "1_RESERVED_1_RESERVED") (pintype "bidirectional"))
    )
    (net (code "64") (name "unconnected-(U$2-Pad2_SS_N)") (class "Default")
      (node (ref "U$2") (pin "2_SS_N") (pinfunction "2_SS_N_2_SS_N") (pintype "bidirectional"))
    )
    (net (code "65") (name "unconnected-(U$2-Pad4_EXTINT0)") (class "Default")
      (node (ref "U$2") (pin "4_EXTINT0") (pinfunction "4_EXTINT0_4_EXTINT0") (pintype "bidirectional"))
    )
    (net (code "66") (name "unconnected-(U$2-Pad5_USB_DM)") (class "Default")
      (node (ref "U$2") (pin "5_USB_DM") (pinfunction "5_USB_DM_5_USB_DM") (pintype "bidirectional"))
    )
    (net (code "67") (name "unconnected-(U$2-Pad6_USB_DP)") (class "Default")
      (node (ref "U$2") (pin "6_USB_DP") (pinfunction "6_USB_DP_6_USB_DP") (pintype "bidirectional"))
    )
    (net (code "68") (name "unconnected-(U$2-Pad8_RESERVED)") (class "Default")
      (node (ref "U$2") (pin "8_RESERVED") (pinfunction "8_RESERVED_8_RESERVED") (pintype "bidirectional"))
    )
    (net (code "69") (name "unconnected-(U$2-Pad9_VCC_RF)") (class "Default")
      (node (ref "U$2") (pin "9_VCC_RF") (pinfunction "9_VCC_RF_9_VCC_RF") (pintype "bidirectional"))
    )
    (net (code "70") (name "unconnected-(U$2-Pad11_RF_IN)") (class "Default")
      (node (ref "U$2") (pin "11_RF_IN") (pinfunction "11_RF_IN_11_RF_IN") (pintype "bidirectional"))
    )
    (net (code "71") (name "unconnected-(U$2-Pad14_MOSI{slash}CFG_COM0)") (class "Default")
      (node (ref "U$2") (pin "14_MOSI/CFG_COM0") (pinfunction "14_MOSI/CFG_COM0_14_MOSI/CFG_COM0") (pintype "bidirectional"))
    )
    (net (code "72") (name "unconnected-(U$2-Pad15_MISO{slash}CFG_COM1)") (class "Default")
      (node (ref "U$2") (pin "15_MISO/CFG_COM1") (pinfunction "15_MISO/CFG_COM1_15_MISO/CFG_COM1") (pintype "bidirectional"))
    )
    (net (code "73") (name "unconnected-(U$2-Pad16_CFG_CPS0{slash}SCK)") (class "Default")
      (node (ref "U$2") (pin "16_CFG_CPS0/SCK") (pinfunction "16_CFG_CPS0/SCK_16_CFG_CPS0/SCK") (pintype "bidirectional"))
    )
    (net (code "74") (name "unconnected-(U$2-Pad17_RESERVED)") (class "Default")
      (node (ref "U$2") (pin "17_RESERVED") (pinfunction "17_RESERVED_17_RESERVED") (pintype "bidirectional"))
    )
    (net (code "75") (name "unconnected-(U$2-Pad18_SDA2)") (class "Default")
      (node (ref "U$2") (pin "18_SDA2") (pinfunction "18_SDA2_18_SDA2") (pintype "bidirectional"))
    )
    (net (code "76") (name "unconnected-(U$2-Pad19_SCL2)") (class "Default")
      (node (ref "U$2") (pin "19_SCL2") (pinfunction "19_SCL2_19_SCL2") (pintype "bidirectional"))
    )
    (net (code "77") (name "unconnected-(U1-NC-Pad3)") (class "Default")
      (node (ref "U1") (pin "3") (pinfunction "NC_3") (pintype "bidirectional"))
    )
    (net (code "78") (name "unconnected-(U1-NC-Pad10)") (class "Default")
      (node (ref "U1") (pin "10") (pinfunction "NC_10") (pintype "bidirectional"))
    )
    (net (code "79") (name "unconnected-(U1-NC-Pad11)") (class "Default")
      (node (ref "U1") (pin "11") (pinfunction "NC_11") (pintype "bidirectional"))
    )
    (net (code "80") (name "unconnected-(U2-NC-Pad3)") (class "Default")
      (node (ref "U2") (pin "3") (pinfunction "NC_3") (pintype "bidirectional"))
    )
    (net (code "81") (name "unconnected-(U2-NC-Pad5)") (class "Default")
      (node (ref "U2") (pin "5") (pinfunction "NC_5") (pintype "bidirectional"))
    )
    (net (code "82") (name "unconnected-(U2-NC-Pad6)") (class "Default")
      (node (ref "U2") (pin "6") (pinfunction "NC_6") (pintype "bidirectional"))
    )
    (net (code "83") (name "unconnected-(U2-NC-Pad7)") (class "Default")
      (node (ref "U2") (pin "7") (pinfunction "NC_7") (pintype "bidirectional"))
    )
    (net (code "84") (name "unconnected-(U2-NC-Pad14)") (class "Default")
      (node (ref "U2") (pin "14") (pinfunction "NC_14") (pintype "bidirectional"))
    )
    (net (code "85") (name "unconnected-(U4-NC{slash}DOUT-Pad6)") (class "Default")
      (node (ref "U4") (pin "6") (pinfunction "NC/DOUT_6") (pintype "bidirectional"))
    )
  )
)
